# Marvin_0_5_2.net
KiCad netlist of a schematic drawn in EAGLE
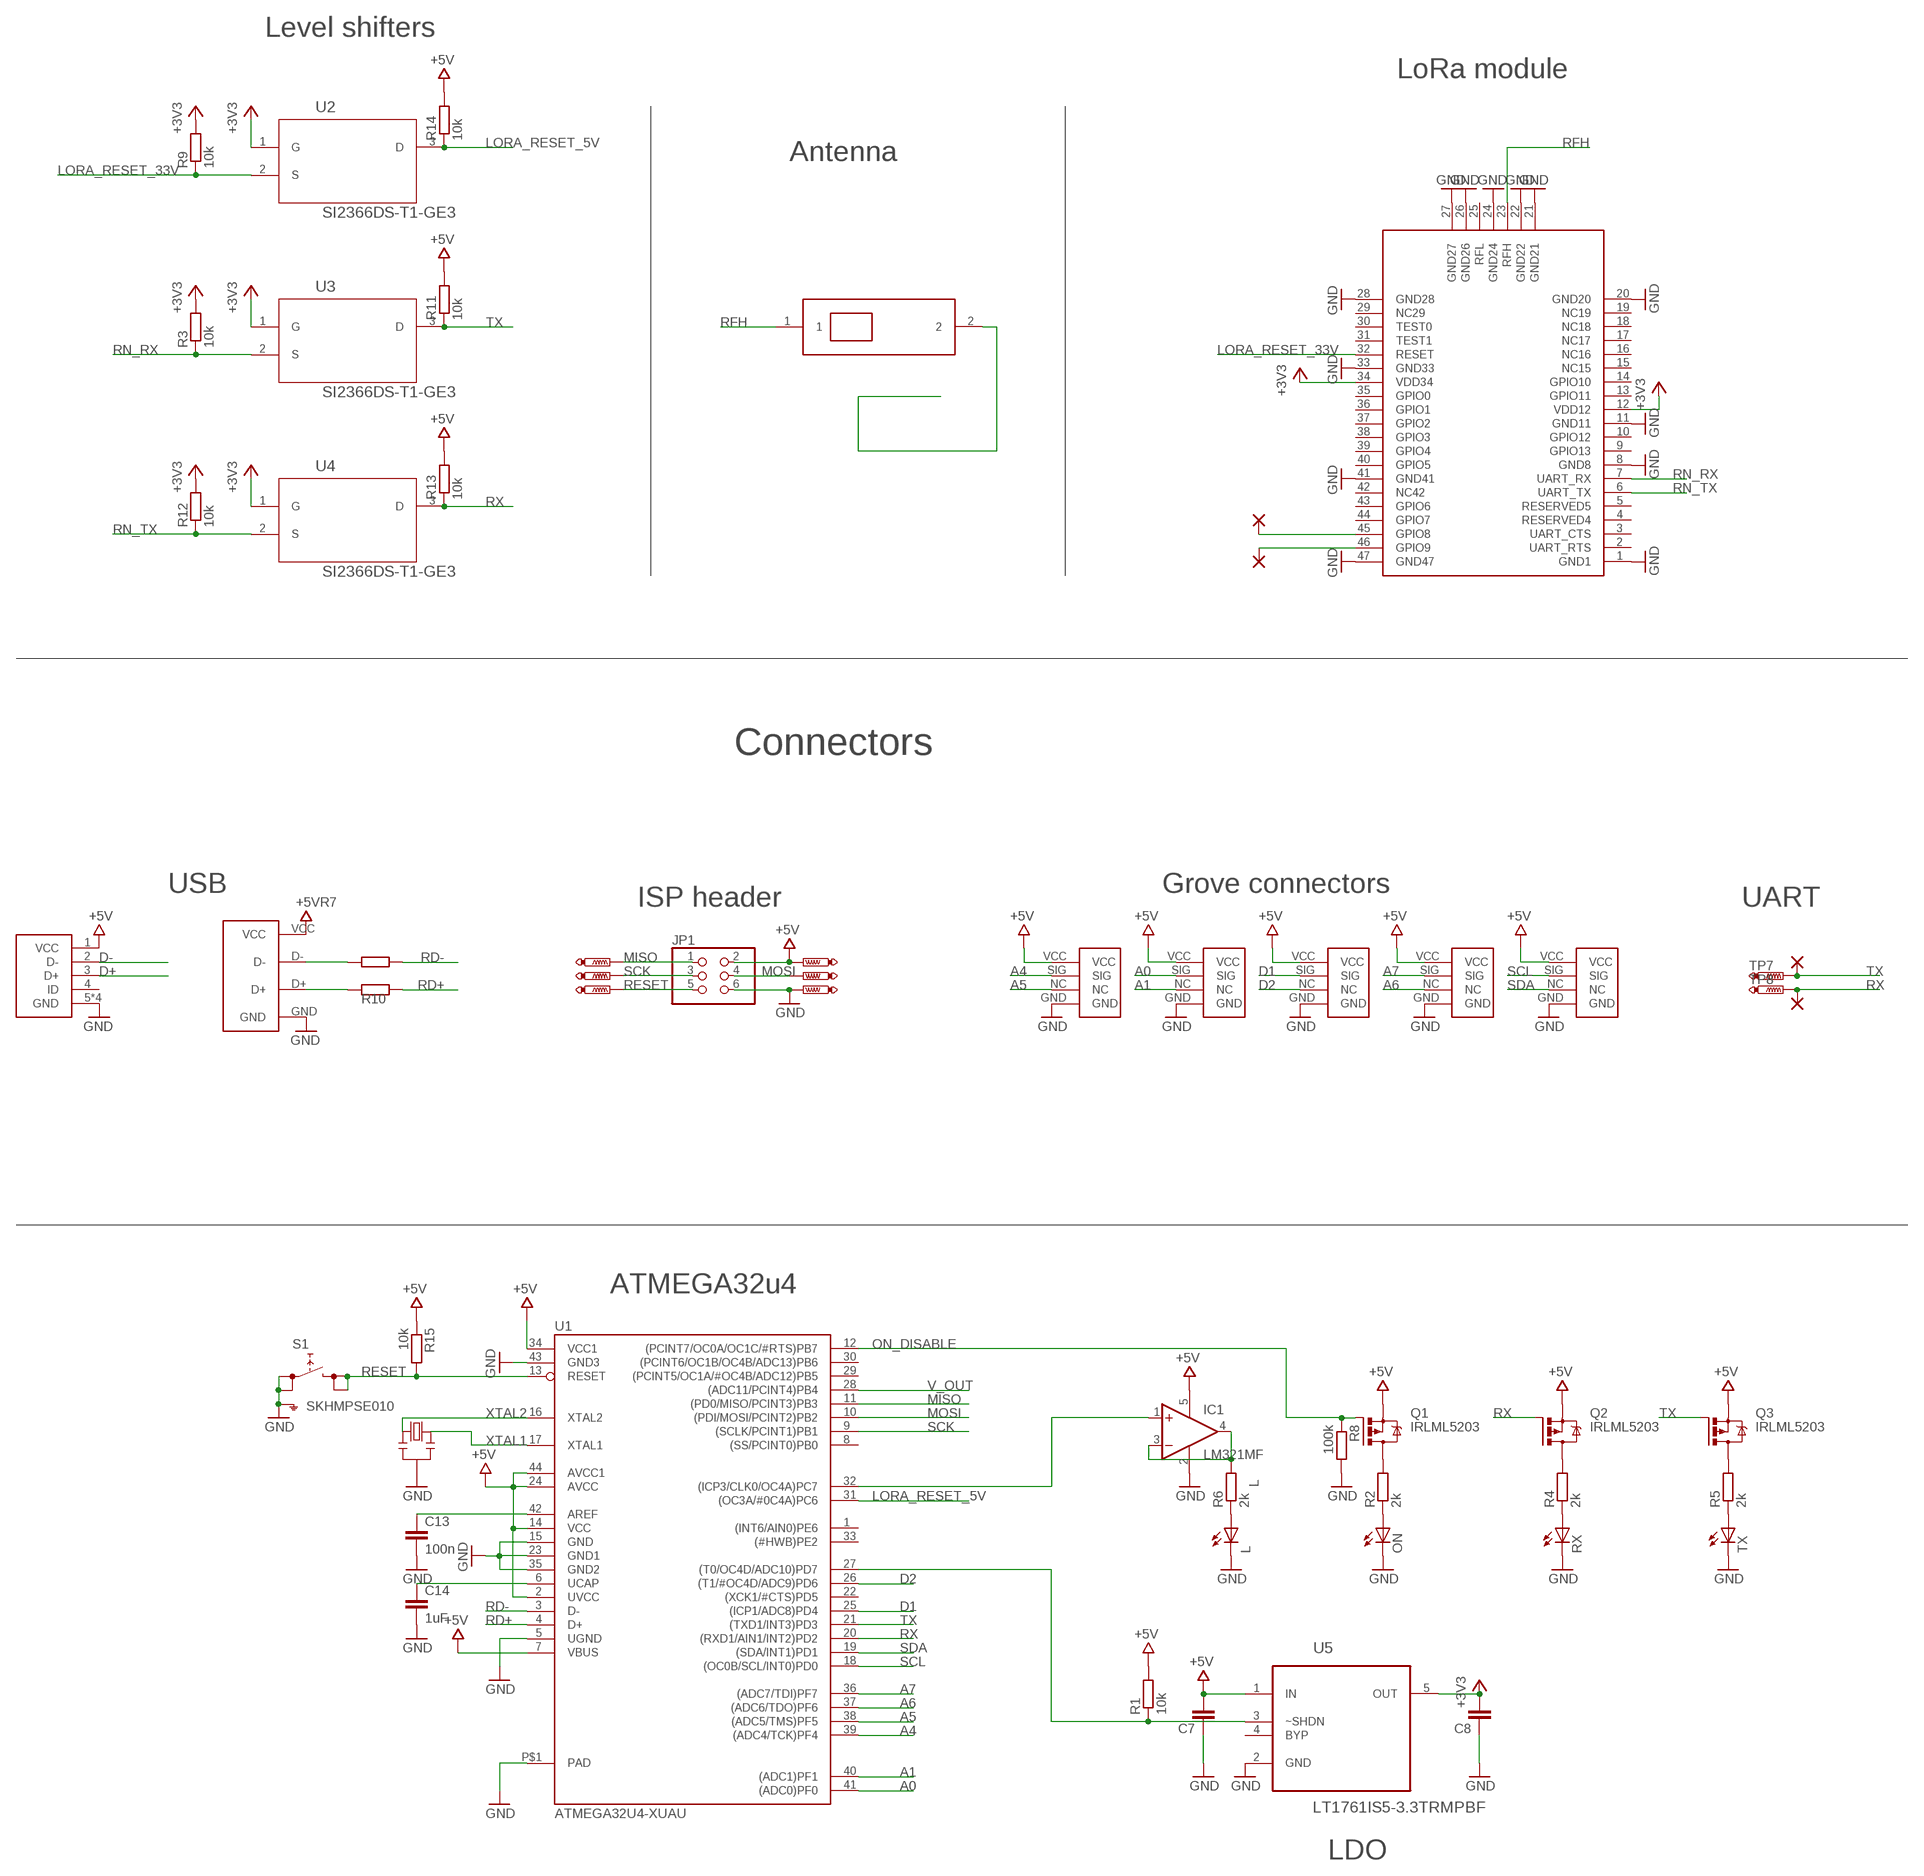
[diagram p0: schematic, sheet 1]

(export (version "E")
  (design (tool "Eeschema 10.0.6"))
  (components
    (comp (ref "A1")
      (value "GROVE")
      (footprint "eagle-import:4POS2MM")
      (libsource (lib "eagle-import") (part "GROVE"))
    )
    (comp (ref "A2")
      (value "GROVE")
      (footprint "eagle-import:4POS2MM")
      (libsource (lib "eagle-import") (part "GROVE"))
    )
    (comp (ref "A3")
      (value "GROVE")
      (footprint "eagle-import:4POS2MM")
      (libsource (lib "eagle-import") (part "GROVE"))
    )
    (comp (ref "C7")
      (value "C-EUC0603")
      (footprint "eagle-import:C0603")
      (libsource (lib "eagle-import") (part "rcl_C-EUC0603"))
    )
    (comp (ref "C8")
      (value "C-EUC0603")
      (footprint "eagle-import:C0603")
      (libsource (lib "eagle-import") (part "rcl_C-EUC0603"))
    )
    (comp (ref "C13")
      (value "100n")
      (footprint "eagle-import:C0603K")
      (libsource (lib "eagle-import") (part "C-EUC0603K"))
    )
    (comp (ref "C14")
      (value "1uF")
      (footprint "eagle-import:C0603K")
      (libsource (lib "eagle-import") (part "C-EUC0603K"))
    )
    (comp (ref "D2")
      (value "GROVE")
      (footprint "eagle-import:4POS2MM")
      (libsource (lib "eagle-import") (part "GROVE"))
    )
    (comp (ref "D2/I2C")
      (value "GROVE")
      (footprint "eagle-import:4POS2MM")
      (libsource (lib "eagle-import") (part "GROVE"))
    )
    (comp (ref "IC1")
      (value "LM321MF")
      (footprint "eagle-import:SOT23-5")
      (libsource (lib "eagle-import") (part "LM321?MF"))
    )
    (comp (ref "JP1")
      (value "PINHD-2X3")
      (footprint "eagle-import:2X03")
      (libsource (lib "eagle-import") (part "PINHD-2X3"))
    )
    (comp (ref "L")
      (value "LEDSML0603")
      (footprint "eagle-import:SML0603")
      (libsource (lib "eagle-import") (part "LEDSML0603"))
    )
    (comp (ref "ON")
      (value "LEDSML0603")
      (footprint "eagle-import:SML0603")
      (libsource (lib "eagle-import") (part "LEDSML0603"))
    )
    (comp (ref "PAD1")
      (value "WIREPAD1,6/0,9")
      (footprint "eagle-import:1,6_0,9")
      (libsource (lib "eagle-import") (part "WIREPAD1,6/0,9"))
    )
    (comp (ref "PAD2")
      (value "WIREPAD1,6/0,9")
      (footprint "eagle-import:1,6_0,9")
      (libsource (lib "eagle-import") (part "WIREPAD1,6/0,9"))
    )
    (comp (ref "PAD3")
      (value "WIREPAD1,6/0,9")
      (footprint "eagle-import:1,6_0,9")
      (libsource (lib "eagle-import") (part "WIREPAD1,6/0,9"))
    )
    (comp (ref "PAD4")
      (value "WIREPAD1,6/0,9")
      (footprint "eagle-import:1,6_0,9")
      (libsource (lib "eagle-import") (part "WIREPAD1,6/0,9"))
    )
    (comp (ref "Q1")
      (value "IRLML5203")
      (footprint "eagle-import:MICRO3")
      (libsource (lib "eagle-import") (part "IRLML5203"))
    )
    (comp (ref "Q2")
      (value "IRLML5203")
      (footprint "eagle-import:MICRO3")
      (libsource (lib "eagle-import") (part "IRLML5203"))
    )
    (comp (ref "Q3")
      (value "IRLML5203")
      (footprint "eagle-import:MICRO3")
      (libsource (lib "eagle-import") (part "IRLML5203"))
    )
    (comp (ref "R1")
      (value "10k")
      (footprint "eagle-import:R0603")
      (libsource (lib "eagle-import") (part "rcl_R-EU_R0603"))
    )
    (comp (ref "R2")
      (value "2k")
      (footprint "eagle-import:R0603")
      (libsource (lib "eagle-import") (part "rcl_R-EU_R0603"))
    )
    (comp (ref "R3")
      (value "10k")
      (footprint "eagle-import:R0603")
      (libsource (lib "eagle-import") (part "rcl_R-EU_R0603"))
    )
    (comp (ref "R4")
      (value "2k")
      (footprint "eagle-import:R0603")
      (libsource (lib "eagle-import") (part "rcl_R-EU_R0603"))
    )
    (comp (ref "R5")
      (value "2k")
      (footprint "eagle-import:R0603")
      (libsource (lib "eagle-import") (part "rcl_R-EU_R0603"))
    )
    (comp (ref "R6")
      (value "2k")
      (footprint "eagle-import:R0603")
      (libsource (lib "eagle-import") (part "rcl_R-EU_R0603"))
    )
    (comp (ref "R7")
      (value "30")
      (footprint "eagle-import:R0603-ROUND")
      (libsource (lib "eagle-import") (part "R-EU_R0603"))
    )
    (comp (ref "R8")
      (value "100k")
      (footprint "eagle-import:R0603")
      (libsource (lib "eagle-import") (part "rcl_R-EU_R0603"))
    )
    (comp (ref "R9")
      (value "10k")
      (footprint "eagle-import:R0603")
      (libsource (lib "eagle-import") (part "rcl_R-EU_R0603"))
    )
    (comp (ref "R10")
      (value "30")
      (footprint "eagle-import:R0603-ROUND")
      (libsource (lib "eagle-import") (part "R-EU_R0603"))
    )
    (comp (ref "R11")
      (value "10k")
      (footprint "eagle-import:R0603")
      (libsource (lib "eagle-import") (part "rcl_R-EU_R0603"))
    )
    (comp (ref "R12")
      (value "10k")
      (footprint "eagle-import:R0603")
      (libsource (lib "eagle-import") (part "rcl_R-EU_R0603"))
    )
    (comp (ref "R13")
      (value "10k")
      (footprint "eagle-import:R0603")
      (libsource (lib "eagle-import") (part "rcl_R-EU_R0603"))
    )
    (comp (ref "R14")
      (value "10k")
      (footprint "eagle-import:R0603")
      (libsource (lib "eagle-import") (part "rcl_R-EU_R0603"))
    )
    (comp (ref "R15")
      (value "10k")
      (footprint "eagle-import:R0603")
      (libsource (lib "eagle-import") (part "rcl_R-EU_R0603"))
    )
    (comp (ref "RX")
      (value "LEDSML0603")
      (footprint "eagle-import:SML0603")
      (libsource (lib "eagle-import") (part "LEDSML0603"))
    )
    (comp (ref "S1")
      (value "SKHMPSE010")
      (footprint "eagle-import:SKHMPXE010")
      (libsource (lib "eagle-import") (part "SKHMPE010S"))
    )
    (comp (ref "TP1")
      (value "PTR1B1,27")
      (footprint "eagle-import:B1,27")
      (libsource (lib "eagle-import") (part "PTR1B1,27"))
    )
    (comp (ref "TP2")
      (value "PTR1B1,27")
      (footprint "eagle-import:B1,27")
      (libsource (lib "eagle-import") (part "PTR1B1,27"))
    )
    (comp (ref "TP3")
      (value "PTR1B1,27")
      (footprint "eagle-import:B1,27")
      (libsource (lib "eagle-import") (part "PTR1B1,27"))
    )
    (comp (ref "TP4")
      (value "PTR1B1,27")
      (footprint "eagle-import:B1,27")
      (libsource (lib "eagle-import") (part "PTR1B1,27"))
    )
    (comp (ref "TP5")
      (value "PTR1B1,27")
      (footprint "eagle-import:B1,27")
      (libsource (lib "eagle-import") (part "PTR1B1,27"))
    )
    (comp (ref "TP6")
      (value "PTR1B1,27")
      (footprint "eagle-import:B1,27")
      (libsource (lib "eagle-import") (part "PTR1B1,27"))
    )
    (comp (ref "TP7")
      (value "PTR1B1,27")
      (footprint "eagle-import:B1,27")
      (libsource (lib "eagle-import") (part "PTR1B1,27"))
    )
    (comp (ref "TP8")
      (value "PTR1B1,27")
      (footprint "eagle-import:B1,27")
      (libsource (lib "eagle-import") (part "PTR1B1,27"))
    )
    (comp (ref "TX")
      (value "LEDSML0603")
      (footprint "eagle-import:SML0603")
      (libsource (lib "eagle-import") (part "LEDSML0603"))
    )
    (comp (ref "U$1")
      (value "RN2483")
      (footprint "eagle-import:RN2483")
      (libsource (lib "eagle-import") (part "RN2483"))
    )
    (comp (ref "U$3")
      (value "USBA")
      (footprint "eagle-import:USBAPLUG")
      (libsource (lib "eagle-import") (part "USBA"))
    )
    (comp (ref "U$16")
      (value "USB-VERTICAL")
      (footprint "eagle-import:MICROUSBVERTICAL")
      (libsource (lib "eagle-import") (part "USB-VERTICAL"))
    )
    (comp (ref "U$25")
      (value "868AT")
      (footprint "eagle-import:868AT")
      (libsource (lib "eagle-import") (part "868AT"))
    )
    (comp (ref "U1")
      (value "ATMEGA32U4-XUAU")
      (footprint "eagle-import:TQFP44-PAD")
      (libsource (lib "eagle-import") (part "ATMEGA32U4-XUAU"))
    )
    (comp (ref "U2")
      (value "SI2366DS-T1-GE3")
      (footprint "eagle-import:SOT95P237X112-3N")
      (libsource (lib "eagle-import") (part "SI2366DS-T1-GE3"))
    )
    (comp (ref "U3")
      (value "SI2366DS-T1-GE3")
      (footprint "eagle-import:SOT95P237X112-3N")
      (libsource (lib "eagle-import") (part "SI2366DS-T1-GE3"))
    )
    (comp (ref "U4")
      (value "SI2366DS-T1-GE3")
      (footprint "eagle-import:SOT95P237X112-3N")
      (libsource (lib "eagle-import") (part "SI2366DS-T1-GE3"))
    )
    (comp (ref "U5")
      (value "LT1761IS5-3.3TRMPBF")
      (footprint "eagle-import:SOT95P280X100-5N")
      (fields (field (name "MPN") "LT1761IS5-3.3#TRMPBF"))
      (libsource (lib "eagle-import") (part "LT1761IS5-3.3TRMPBF"))
    )
    (comp (ref "Y1")
      (value "CSTCE16M0V53-R0 16MHZ")
      (footprint "eagle-import:RESONATOR")
      (libsource (lib "eagle-import") (part "RESONATORMU"))
    )
  )
  (nets
    (net (code "1") (name "+3V3") (class "Default")
      (node (ref "C8") (pin "2") (pinfunction "2_2") (pintype "passive"))
      (node (ref "R12") (pin "2") (pinfunction "2_2") (pintype "passive"))
      (node (ref "R3") (pin "2") (pinfunction "2_2") (pintype "passive"))
      (node (ref "R9") (pin "2") (pinfunction "2_2") (pintype "passive"))
      (node (ref "U$1") (pin "12") (pinfunction "VDD12_12") (pintype "bidirectional"))
      (node (ref "U$1") (pin "34") (pinfunction "VDD34_34") (pintype "bidirectional"))
      (node (ref "U2") (pin "1") (pinfunction "G_1") (pintype "passive"))
      (node (ref "U3") (pin "1") (pinfunction "G_1") (pintype "passive"))
      (node (ref "U4") (pin "1") (pinfunction "G_1") (pintype "passive"))
      (node (ref "U5") (pin "5") (pinfunction "OUT_5") (pintype "output"))
    )
    (net (code "2") (name "+5V") (class "Default")
      (node (ref "A1") (pin "VCC") (pinfunction "VCC_VCC") (pintype "bidirectional"))
      (node (ref "A2") (pin "VCC") (pinfunction "VCC_VCC") (pintype "bidirectional"))
      (node (ref "A3") (pin "VCC") (pinfunction "VCC_VCC") (pintype "bidirectional"))
      (node (ref "C7") (pin "2") (pinfunction "2_2") (pintype "passive"))
      (node (ref "D2") (pin "VCC") (pinfunction "VCC_VCC") (pintype "bidirectional"))
      (node (ref "D2/I2C") (pin "VCC") (pinfunction "VCC_VCC") (pintype "bidirectional"))
      (node (ref "IC1") (pin "5") (pinfunction "V+_5") (pintype "power_in"))
      (node (ref "JP1") (pin "2") (pinfunction "2_2") (pintype "passive"))
      (node (ref "Q1") (pin "2") (pinfunction "S_2") (pintype "passive"))
      (node (ref "Q2") (pin "2") (pinfunction "S_2") (pintype "passive"))
      (node (ref "Q3") (pin "2") (pinfunction "S_2") (pintype "passive"))
      (node (ref "R1") (pin "2") (pinfunction "2_2") (pintype "passive"))
      (node (ref "R11") (pin "2") (pinfunction "2_2") (pintype "passive"))
      (node (ref "R13") (pin "2") (pinfunction "2_2") (pintype "passive"))
      (node (ref "R14") (pin "2") (pinfunction "2_2") (pintype "passive"))
      (node (ref "R15") (pin "1") (pinfunction "1_1") (pintype "passive"))
      (node (ref "TP6") (pin "TP") (pinfunction "TP_TP") (pintype "input"))
      (node (ref "U$16") (pin "1") (pinfunction "VCC_1") (pintype "bidirectional"))
      (node (ref "U$3") (pin "VCC") (pinfunction "VCC_VCC") (pintype "bidirectional"))
      (node (ref "U1") (pin "14") (pinfunction "VCC_14") (pintype "power_in"))
      (node (ref "U1") (pin "2") (pinfunction "UVCC_2") (pintype "power_in"))
      (node (ref "U1") (pin "24") (pinfunction "AVCC_24") (pintype "power_in"))
      (node (ref "U1") (pin "34") (pinfunction "VCC1_34") (pintype "power_in"))
      (node (ref "U1") (pin "44") (pinfunction "AVCC1_44") (pintype "power_in"))
      (node (ref "U1") (pin "7") (pinfunction "VBUS_7") (pintype "input"))
      (node (ref "U5") (pin "1") (pinfunction "IN_1") (pintype "input"))
    )
    (net (code "3") (name "/A0") (class "Default")
      (node (ref "A1") (pin "SIG") (pinfunction "SIG_SIG") (pintype "bidirectional"))
      (node (ref "U1") (pin "41") (pinfunction "(ADC0)PF0_41") (pintype "bidirectional"))
    )
    (net (code "4") (name "/A1") (class "Default")
      (node (ref "A1") (pin "NC") (pinfunction "NC_NC") (pintype "bidirectional"))
      (node (ref "U1") (pin "40") (pinfunction "(ADC1)PF1_40") (pintype "bidirectional"))
    )
    (net (code "5") (name "/A4") (class "Default")
      (node (ref "A2") (pin "SIG") (pinfunction "SIG_SIG") (pintype "bidirectional"))
      (node (ref "U1") (pin "39") (pinfunction "(ADC4/TCK)PF4_39") (pintype "bidirectional"))
    )
    (net (code "6") (name "/A5") (class "Default")
      (node (ref "A2") (pin "NC") (pinfunction "NC_NC") (pintype "bidirectional"))
      (node (ref "U1") (pin "38") (pinfunction "(ADC5/TMS)PF5_38") (pintype "bidirectional"))
    )
    (net (code "7") (name "/A6") (class "Default")
      (node (ref "A3") (pin "NC") (pinfunction "NC_NC") (pintype "bidirectional"))
      (node (ref "U1") (pin "37") (pinfunction "(ADC6/TDO)PF6_37") (pintype "bidirectional"))
    )
    (net (code "8") (name "/A7") (class "Default")
      (node (ref "A3") (pin "SIG") (pinfunction "SIG_SIG") (pintype "bidirectional"))
      (node (ref "U1") (pin "36") (pinfunction "(ADC7/TDI)PF7_36") (pintype "bidirectional"))
    )
    (net (code "9") (name "/D+") (class "Default")
      (node (ref "R10") (pin "2") (pinfunction "2_2") (pintype "passive"))
      (node (ref "U$16") (pin "3") (pinfunction "D+_3") (pintype "bidirectional"))
      (node (ref "U$3") (pin "D+") (pinfunction "D+_D+") (pintype "bidirectional"))
    )
    (net (code "10") (name "/D-") (class "Default")
      (node (ref "R7") (pin "2") (pinfunction "2_2") (pintype "passive"))
      (node (ref "U$16") (pin "2") (pinfunction "D-_2") (pintype "bidirectional"))
      (node (ref "U$3") (pin "D-") (pinfunction "D-_D-") (pintype "bidirectional"))
    )
    (net (code "11") (name "/D1") (class "Default")
      (node (ref "D2") (pin "SIG") (pinfunction "SIG_SIG") (pintype "bidirectional"))
      (node (ref "U1") (pin "25") (pinfunction "(ICP1/ADC8)PD4_25") (pintype "bidirectional"))
    )
    (net (code "12") (name "/D2") (class "Default")
      (node (ref "D2") (pin "NC") (pinfunction "NC_NC") (pintype "bidirectional"))
      (node (ref "U1") (pin "26") (pinfunction "(T1/#OC4D/ADC9)PD6_26") (pintype "bidirectional"))
    )
    (net (code "13") (name "/L") (class "Default")
      (node (ref "IC1") (pin "3") (pinfunction "-IN_3") (pintype "input"))
      (node (ref "IC1") (pin "4") (pinfunction "OUT_4") (pintype "output"))
      (node (ref "R6") (pin "2") (pinfunction "2_2") (pintype "passive"))
    )
    (net (code "14") (name "/LORA_RESET_5V") (class "Default")
      (node (ref "R14") (pin "1") (pinfunction "1_1") (pintype "passive"))
      (node (ref "U1") (pin "31") (pinfunction "(OC3A/#0C4A)PC6_31") (pintype "bidirectional"))
      (node (ref "U2") (pin "3") (pinfunction "D_3") (pintype "passive"))
    )
    (net (code "15") (name "/LORA_RESET_33V") (class "Default")
      (node (ref "R9") (pin "1") (pinfunction "1_1") (pintype "passive"))
      (node (ref "U$1") (pin "32") (pinfunction "RESET_32") (pintype "bidirectional"))
      (node (ref "U2") (pin "2") (pinfunction "S_2") (pintype "passive"))
    )
    (net (code "16") (name "/MISO") (class "Default")
      (node (ref "JP1") (pin "1") (pinfunction "1_1") (pintype "passive"))
      (node (ref "TP1") (pin "TP") (pinfunction "TP_TP") (pintype "input"))
      (node (ref "U1") (pin "11") (pinfunction "(PD0/MISO/PCINT3)PB3_11") (pintype "bidirectional"))
    )
    (net (code "17") (name "/MOSI") (class "Default")
      (node (ref "JP1") (pin "4") (pinfunction "4_4") (pintype "passive"))
      (node (ref "TP5") (pin "TP") (pinfunction "TP_TP") (pintype "input"))
      (node (ref "U1") (pin "10") (pinfunction "(PDI/MOSI/PCINT2)PB2_10") (pintype "bidirectional"))
    )
    (net (code "18") (name "/ON_DISABLE") (class "Default")
      (node (ref "Q1") (pin "1") (pinfunction "G_1") (pintype "passive"))
      (node (ref "R8") (pin "1") (pinfunction "1_1") (pintype "passive"))
      (node (ref "U1") (pin "12") (pinfunction "(PCINT7/OC0A/OC1C/#RTS)PB7_12") (pintype "bidirectional"))
    )
    (net (code "19") (name "/RD+") (class "Default")
      (node (ref "R10") (pin "1") (pinfunction "1_1") (pintype "passive"))
      (node (ref "U1") (pin "4") (pinfunction "D+_4") (pintype "bidirectional"))
    )
    (net (code "20") (name "/RD-") (class "Default")
      (node (ref "R7") (pin "1") (pinfunction "1_1") (pintype "passive"))
      (node (ref "U1") (pin "3") (pinfunction "D-_3") (pintype "bidirectional"))
    )
    (net (code "21") (name "/RESET") (class "Default")
      (node (ref "JP1") (pin "5") (pinfunction "5_5") (pintype "passive"))
      (node (ref "R15") (pin "2") (pinfunction "2_2") (pintype "passive"))
      (node (ref "S1") (pin "3") (pinfunction "2.1_3") (pintype "passive"))
      (node (ref "S1") (pin "4") (pinfunction "2.2_4") (pintype "passive"))
      (node (ref "TP3") (pin "TP") (pinfunction "TP_TP") (pintype "input"))
      (node (ref "U1") (pin "13") (pinfunction "RESET_13") (pintype "input"))
    )
    (net (code "22") (name "/RFH") (class "Default")
      (node (ref "U$1") (pin "23") (pinfunction "RFH_23") (pintype "bidirectional"))
      (node (ref "U$25") (pin "1") (pinfunction "1_1") (pintype "bidirectional"))
    )
    (net (code "23") (name "/RN_RX") (class "Default")
      (node (ref "R3") (pin "1") (pinfunction "1_1") (pintype "passive"))
      (node (ref "U$1") (pin "7") (pinfunction "UART_RX_7") (pintype "bidirectional"))
      (node (ref "U3") (pin "2") (pinfunction "S_2") (pintype "passive"))
    )
    (net (code "24") (name "/RN_TX") (class "Default")
      (node (ref "R12") (pin "1") (pinfunction "1_1") (pintype "passive"))
      (node (ref "U$1") (pin "6") (pinfunction "UART_TX_6") (pintype "bidirectional"))
      (node (ref "U4") (pin "2") (pinfunction "S_2") (pintype "passive"))
    )
    (net (code "25") (name "/RX") (class "Default")
      (node (ref "PAD2") (pin "1") (pinfunction "P_1") (pintype "passive"))
      (node (ref "Q2") (pin "1") (pinfunction "G_1") (pintype "passive"))
      (node (ref "R13") (pin "1") (pinfunction "1_1") (pintype "passive"))
      (node (ref "TP8") (pin "TP") (pinfunction "TP_TP") (pintype "input"))
      (node (ref "U1") (pin "20") (pinfunction "(RXD1/AIN1/INT2)PD2_20") (pintype "bidirectional"))
      (node (ref "U4") (pin "3") (pinfunction "D_3") (pintype "passive"))
    )
    (net (code "26") (name "/SCK") (class "Default")
      (node (ref "JP1") (pin "3") (pinfunction "3_3") (pintype "passive"))
      (node (ref "TP2") (pin "TP") (pinfunction "TP_TP") (pintype "input"))
      (node (ref "U1") (pin "9") (pinfunction "(SCLK/PCINT1)PB1_9") (pintype "bidirectional"))
    )
    (net (code "27") (name "/SCL") (class "Default")
      (node (ref "D2/I2C") (pin "SIG") (pinfunction "SIG_SIG") (pintype "bidirectional"))
      (node (ref "U1") (pin "18") (pinfunction "(OC0B/SCL/INT0)PD0_18") (pintype "bidirectional"))
    )
    (net (code "28") (name "/SDA") (class "Default")
      (node (ref "D2/I2C") (pin "NC") (pinfunction "NC_NC") (pintype "bidirectional"))
      (node (ref "U1") (pin "19") (pinfunction "(SDA/INT1)PD1_19") (pintype "bidirectional"))
    )
    (net (code "29") (name "/TX") (class "Default")
      (node (ref "PAD1") (pin "1") (pinfunction "P_1") (pintype "passive"))
      (node (ref "Q3") (pin "1") (pinfunction "G_1") (pintype "passive"))
      (node (ref "R11") (pin "1") (pinfunction "1_1") (pintype "passive"))
      (node (ref "TP7") (pin "TP") (pinfunction "TP_TP") (pintype "input"))
      (node (ref "U1") (pin "21") (pinfunction "(TXD1/INT3)PD3_21") (pintype "bidirectional"))
      (node (ref "U3") (pin "3") (pinfunction "D_3") (pintype "passive"))
    )
    (net (code "30") (name "/V_OUT") (class "Default")
      (node (ref "U1") (pin "28") (pinfunction "(ADC11/PCINT4)PB4_28") (pintype "bidirectional"))
    )
    (net (code "31") (name "/XTAL1") (class "Default")
      (node (ref "U1") (pin "17") (pinfunction "XTAL1_17") (pintype "bidirectional"))
      (node (ref "Y1") (pin "3") (pinfunction "3_3") (pintype "passive"))
    )
    (net (code "32") (name "/XTAL2") (class "Default")
      (node (ref "U1") (pin "16") (pinfunction "XTAL2_16") (pintype "bidirectional"))
      (node (ref "Y1") (pin "1") (pinfunction "1_1") (pintype "passive"))
    )
    (net (code "33") (name "GND") (class "Default")
      (node (ref "A1") (pin "GND") (pinfunction "GND_GND") (pintype "bidirectional"))
      (node (ref "A2") (pin "GND") (pinfunction "GND_GND") (pintype "bidirectional"))
      (node (ref "A3") (pin "GND") (pinfunction "GND_GND") (pintype "bidirectional"))
      (node (ref "C13") (pin "2") (pinfunction "2_2") (pintype "passive"))
      (node (ref "C14") (pin "2") (pinfunction "2_2") (pintype "passive"))
      (node (ref "C7") (pin "1") (pinfunction "1_1") (pintype "passive"))
      (node (ref "C8") (pin "1") (pinfunction "1_1") (pintype "passive"))
      (node (ref "D2") (pin "GND") (pinfunction "GND_GND") (pintype "bidirectional"))
      (node (ref "D2/I2C") (pin "GND") (pinfunction "GND_GND") (pintype "bidirectional"))
      (node (ref "IC1") (pin "2") (pinfunction "V-_2") (pintype "power_in"))
      (node (ref "JP1") (pin "6") (pinfunction "6_6") (pintype "passive"))
      (node (ref "L") (pin "C") (pinfunction "C_C") (pintype "passive"))
      (node (ref "ON") (pin "C") (pinfunction "C_C") (pintype "passive"))
      (node (ref "R8") (pin "2") (pinfunction "2_2") (pintype "passive"))
      (node (ref "RX") (pin "C") (pinfunction "C_C") (pintype "passive"))
      (node (ref "S1") (pin "1") (pinfunction "1.1_1") (pintype "passive"))
      (node (ref "S1") (pin "2") (pinfunction "1.2_2") (pintype "passive"))
      (node (ref "S1") (pin "5") (pinfunction "SH_5") (pintype "passive"))
      (node (ref "TP4") (pin "TP") (pinfunction "TP_TP") (pintype "input"))
      (node (ref "TX") (pin "C") (pinfunction "C_C") (pintype "passive"))
      (node (ref "U$1") (pin "1") (pinfunction "GND1_1") (pintype "bidirectional"))
      (node (ref "U$1") (pin "11") (pinfunction "GND11_11") (pintype "bidirectional"))
      (node (ref "U$1") (pin "20") (pinfunction "GND20_20") (pintype "bidirectional"))
      (node (ref "U$1") (pin "21") (pinfunction "GND21_21") (pintype "bidirectional"))
      (node (ref "U$1") (pin "22") (pinfunction "GND22_22") (pintype "bidirectional"))
      (node (ref "U$1") (pin "24") (pinfunction "GND24_24") (pintype "bidirectional"))
      (node (ref "U$1") (pin "26") (pinfunction "GND26_26") (pintype "bidirectional"))
      (node (ref "U$1") (pin "27") (pinfunction "GND27_27") (pintype "bidirectional"))
      (node (ref "U$1") (pin "28") (pinfunction "GND28_28") (pintype "bidirectional"))
      (node (ref "U$1") (pin "33") (pinfunction "GND33_33") (pintype "bidirectional"))
      (node (ref "U$1") (pin "41") (pinfunction "GND41_41") (pintype "bidirectional"))
      (node (ref "U$1") (pin "47") (pinfunction "GND47_47") (pintype "bidirectional"))
      (node (ref "U$1") (pin "8") (pinfunction "GND8_8") (pintype "bidirectional"))
      (node (ref "U$16") (pin "5") (pinfunction "GND_5") (pintype "bidirectional"))
      (node (ref "U$16") (pin "P$1") (pinfunction "GND_P$1") (pintype "bidirectional"))
      (node (ref "U$16") (pin "P$2") (pinfunction "GND_P$2") (pintype "bidirectional"))
      (node (ref "U$16") (pin "P$3") (pinfunction "GND_P$3") (pintype "bidirectional"))
      (node (ref "U$3") (pin "GND") (pinfunction "GND_GND") (pintype "bidirectional"))
      (node (ref "U1") (pin "15") (pinfunction "GND_15") (pintype "power_in"))
      (node (ref "U1") (pin "23") (pinfunction "GND1_23") (pintype "power_in"))
      (node (ref "U1") (pin "35") (pinfunction "GND2_35") (pintype "power_in"))
      (node (ref "U1") (pin "43") (pinfunction "GND3_43") (pintype "power_in"))
      (node (ref "U1") (pin "5") (pinfunction "UGND_5") (pintype "power_in"))
      (node (ref "U1") (pin "P$1") (pinfunction "PAD_P$1") (pintype "power_in"))
      (node (ref "U5") (pin "2") (pinfunction "GND_2") (pintype "passive"))
      (node (ref "Y1") (pin "2") (pinfunction "2_2") (pintype "passive"))
    )
    (net (code "34") (name "Net-(IC1-+IN)") (class "Default")
      (node (ref "IC1") (pin "1") (pinfunction "+IN_1") (pintype "input"))
      (node (ref "U1") (pin "32") (pinfunction "(ICP3/CLK0/OC4A)PC7_32") (pintype "bidirectional"))
    )
    (net (code "35") (name "Net-(L-PadA)") (class "Default")
      (node (ref "L") (pin "A") (pinfunction "A_A") (pintype "passive"))
      (node (ref "R6") (pin "1") (pinfunction "1_1") (pintype "passive"))
    )
    (net (code "36") (name "Net-(ON-PadA)") (class "Default")
      (node (ref "ON") (pin "A") (pinfunction "A_A") (pintype "passive"))
      (node (ref "R2") (pin "1") (pinfunction "1_1") (pintype "passive"))
    )
    (net (code "37") (name "Net-(PAD3-P)") (class "Default")
      (node (ref "PAD3") (pin "1") (pinfunction "P_1") (pintype "passive"))
      (node (ref "U$1") (pin "46") (pinfunction "GPIO9_46") (pintype "bidirectional"))
    )
    (net (code "38") (name "Net-(PAD4-P)") (class "Default")
      (node (ref "PAD4") (pin "1") (pinfunction "P_1") (pintype "passive"))
      (node (ref "U$1") (pin "45") (pinfunction "GPIO8_45") (pintype "bidirectional"))
    )
    (net (code "39") (name "Net-(Q1-D)") (class "Default")
      (node (ref "Q1") (pin "3") (pinfunction "D_3") (pintype "passive"))
      (node (ref "R2") (pin "2") (pinfunction "2_2") (pintype "passive"))
    )
    (net (code "40") (name "Net-(Q2-D)") (class "Default")
      (node (ref "Q2") (pin "3") (pinfunction "D_3") (pintype "passive"))
      (node (ref "R4") (pin "2") (pinfunction "2_2") (pintype "passive"))
    )
    (net (code "41") (name "Net-(Q3-D)") (class "Default")
      (node (ref "Q3") (pin "3") (pinfunction "D_3") (pintype "passive"))
      (node (ref "R5") (pin "2") (pinfunction "2_2") (pintype "passive"))
    )
    (net (code "42") (name "Net-(R4-Pad1)") (class "Default")
      (node (ref "R4") (pin "1") (pinfunction "1_1") (pintype "passive"))
      (node (ref "RX") (pin "A") (pinfunction "A_A") (pintype "passive"))
    )
    (net (code "43") (name "Net-(R5-Pad1)") (class "Default")
      (node (ref "R5") (pin "1") (pinfunction "1_1") (pintype "passive"))
      (node (ref "TX") (pin "A") (pinfunction "A_A") (pintype "passive"))
    )
    (net (code "44") (name "Net-(U1-(T0{slash}OC4D{slash}ADC10)PD7)") (class "Default")
      (node (ref "R1") (pin "1") (pinfunction "1_1") (pintype "passive"))
      (node (ref "U1") (pin "27") (pinfunction "(T0/OC4D/ADC10)PD7_27") (pintype "bidirectional"))
      (node (ref "U5") (pin "3") (pinfunction "~{SHDN}_3") (pintype "input"))
    )
    (net (code "45") (name "Net-(U1-AREF)") (class "Default")
      (node (ref "C13") (pin "1") (pinfunction "1_1") (pintype "passive"))
      (node (ref "U1") (pin "42") (pinfunction "AREF_42") (pintype "power_in"))
    )
    (net (code "46") (name "Net-(U1-UCAP)") (class "Default")
      (node (ref "C14") (pin "1") (pinfunction "1_1") (pintype "passive"))
      (node (ref "U1") (pin "6") (pinfunction "UCAP_6") (pintype "passive"))
    )
    (net (code "47") (name "unconnected-(U$1-GPIO0-Pad35)") (class "Default")
      (node (ref "U$1") (pin "35") (pinfunction "GPIO0_35") (pintype "bidirectional"))
    )
    (net (code "48") (name "unconnected-(U$1-GPIO1-Pad36)") (class "Default")
      (node (ref "U$1") (pin "36") (pinfunction "GPIO1_36") (pintype "bidirectional"))
    )
    (net (code "49") (name "unconnected-(U$1-GPIO2-Pad37)") (class "Default")
      (node (ref "U$1") (pin "37") (pinfunction "GPIO2_37") (pintype "bidirectional"))
    )
    (net (code "50") (name "unconnected-(U$1-GPIO3-Pad38)") (class "Default")
      (node (ref "U$1") (pin "38") (pinfunction "GPIO3_38") (pintype "bidirectional"))
    )
    (net (code "51") (name "unconnected-(U$1-GPIO4-Pad39)") (class "Default")
      (node (ref "U$1") (pin "39") (pinfunction "GPIO4_39") (pintype "bidirectional"))
    )
    (net (code "52") (name "unconnected-(U$1-GPIO5-Pad40)") (class "Default")
      (node (ref "U$1") (pin "40") (pinfunction "GPIO5_40") (pintype "bidirectional"))
    )
    (net (code "53") (name "unconnected-(U$1-GPIO6-Pad43)") (class "Default")
      (node (ref "U$1") (pin "43") (pinfunction "GPIO6_43") (pintype "bidirectional"))
    )
    (net (code "54") (name "unconnected-(U$1-GPIO7-Pad44)") (class "Default")
      (node (ref "U$1") (pin "44") (pinfunction "GPIO7_44") (pintype "bidirectional"))
    )
    (net (code "55") (name "unconnected-(U$1-GPIO10-Pad14)") (class "Default")
      (node (ref "U$1") (pin "14") (pinfunction "GPIO10_14") (pintype "bidirectional"))
    )
    (net (code "56") (name "unconnected-(U$1-GPIO11-Pad13)") (class "Default")
      (node (ref "U$1") (pin "13") (pinfunction "GPIO11_13") (pintype "bidirectional"))
    )
    (net (code "57") (name "unconnected-(U$1-GPIO12-Pad10)") (class "Default")
      (node (ref "U$1") (pin "10") (pinfunction "GPIO12_10") (pintype "bidirectional"))
    )
    (net (code "58") (name "unconnected-(U$1-GPIO13-Pad9)") (class "Default")
      (node (ref "U$1") (pin "9") (pinfunction "GPIO13_9") (pintype "bidirectional"))
    )
    (net (code "59") (name "unconnected-(U$1-NC15-Pad15)") (class "Default")
      (node (ref "U$1") (pin "15") (pinfunction "NC15_15") (pintype "bidirectional"))
    )
    (net (code "60") (name "unconnected-(U$1-NC16-Pad16)") (class "Default")
      (node (ref "U$1") (pin "16") (pinfunction "NC16_16") (pintype "bidirectional"))
    )
    (net (code "61") (name "unconnected-(U$1-NC17-Pad17)") (class "Default")
      (node (ref "U$1") (pin "17") (pinfunction "NC17_17") (pintype "bidirectional"))
    )
    (net (code "62") (name "unconnected-(U$1-NC18-Pad18)") (class "Default")
      (node (ref "U$1") (pin "18") (pinfunction "NC18_18") (pintype "bidirectional"))
    )
    (net (code "63") (name "unconnected-(U$1-NC19-Pad19)") (class "Default")
      (node (ref "U$1") (pin "19") (pinfunction "NC19_19") (pintype "bidirectional"))
    )
    (net (code "64") (name "unconnected-(U$1-NC29-Pad29)") (class "Default")
      (node (ref "U$1") (pin "29") (pinfunction "NC29_29") (pintype "bidirectional"))
    )
    (net (code "65") (name "unconnected-(U$1-NC42-Pad42)") (class "Default")
      (node (ref "U$1") (pin "42") (pinfunction "NC42_42") (pintype "bidirectional"))
    )
    (net (code "66") (name "unconnected-(U$1-RESERVED4-Pad4)") (class "Default")
      (node (ref "U$1") (pin "4") (pinfunction "RESERVED4_4") (pintype "bidirectional"))
    )
    (net (code "67") (name "unconnected-(U$1-RESERVED5-Pad5)") (class "Default")
      (node (ref "U$1") (pin "5") (pinfunction "RESERVED5_5") (pintype "bidirectional"))
    )
    (net (code "68") (name "unconnected-(U$1-RFL-Pad25)") (class "Default")
      (node (ref "U$1") (pin "25") (pinfunction "RFL_25") (pintype "bidirectional"))
    )
    (net (code "69") (name "unconnected-(U$1-TEST0-Pad30)") (class "Default")
      (node (ref "U$1") (pin "30") (pinfunction "TEST0_30") (pintype "bidirectional"))
    )
    (net (code "70") (name "unconnected-(U$1-TEST1-Pad31)") (class "Default")
      (node (ref "U$1") (pin "31") (pinfunction "TEST1_31") (pintype "bidirectional"))
    )
    (net (code "71") (name "unconnected-(U$1-UART_CTS-Pad3)") (class "Default")
      (node (ref "U$1") (pin "3") (pinfunction "UART_CTS_3") (pintype "bidirectional"))
    )
    (net (code "72") (name "unconnected-(U$1-UART_RTS-Pad2)") (class "Default")
      (node (ref "U$1") (pin "2") (pinfunction "UART_RTS_2") (pintype "bidirectional"))
    )
    (net (code "73") (name "unconnected-(U$16-ID-Pad4)") (class "Default")
      (node (ref "U$16") (pin "4") (pinfunction "ID_4") (pintype "bidirectional"))
    )
    (net (code "74") (name "unconnected-(U$25-Pad2)") (class "Default")
      (node (ref "U$25") (pin "2") (pinfunction "2_2") (pintype "bidirectional"))
    )
    (net (code "75") (name "unconnected-(U1-(#HWB)PE2-Pad33)") (class "Default")
      (node (ref "U1") (pin "33") (pinfunction "(#HWB)PE2_33") (pintype "bidirectional"))
    )
    (net (code "76") (name "unconnected-(U1-(INT6{slash}AIN0)PE6-Pad1)") (class "Default")
      (node (ref "U1") (pin "1") (pinfunction "(INT6/AIN0)PE6_1") (pintype "bidirectional"))
    )
    (net (code "77") (name "unconnected-(U1-(PCINT5{slash}OC1A{slash}#OC4B{slash}ADC12)PB5-Pad29)") (class "Default")
      (node (ref "U1") (pin "29") (pinfunction "(PCINT5/OC1A/#OC4B/ADC12)PB5_29") (pintype "bidirectional"))
    )
    (net (code "78") (name "unconnected-(U1-(PCINT6{slash}OC1B{slash}OC4B{slash}ADC13)PB6-Pad30)") (class "Default")
      (node (ref "U1") (pin "30") (pinfunction "(PCINT6/OC1B/OC4B/ADC13)PB6_30") (pintype "bidirectional"))
    )
    (net (code "79") (name "unconnected-(U1-(SS{slash}PCINT0)PB0-Pad8)") (class "Default")
      (node (ref "U1") (pin "8") (pinfunction "(SS/PCINT0)PB0_8") (pintype "bidirectional"))
    )
    (net (code "80") (name "unconnected-(U1-(XCK1{slash}#CTS)PD5-Pad22)") (class "Default")
      (node (ref "U1") (pin "22") (pinfunction "(XCK1/#CTS)PD5_22") (pintype "bidirectional"))
    )
    (net (code "81") (name "unconnected-(U5-BYP-Pad4)") (class "Default")
      (node (ref "U5") (pin "4") (pinfunction "BYP_4") (pintype "passive"))
    )
  )
)
